# UBX_NORA_B1_SCHEM_0005_Interface_Isolati.net
KiCad netlist of a schematic drawn in Altium Designer
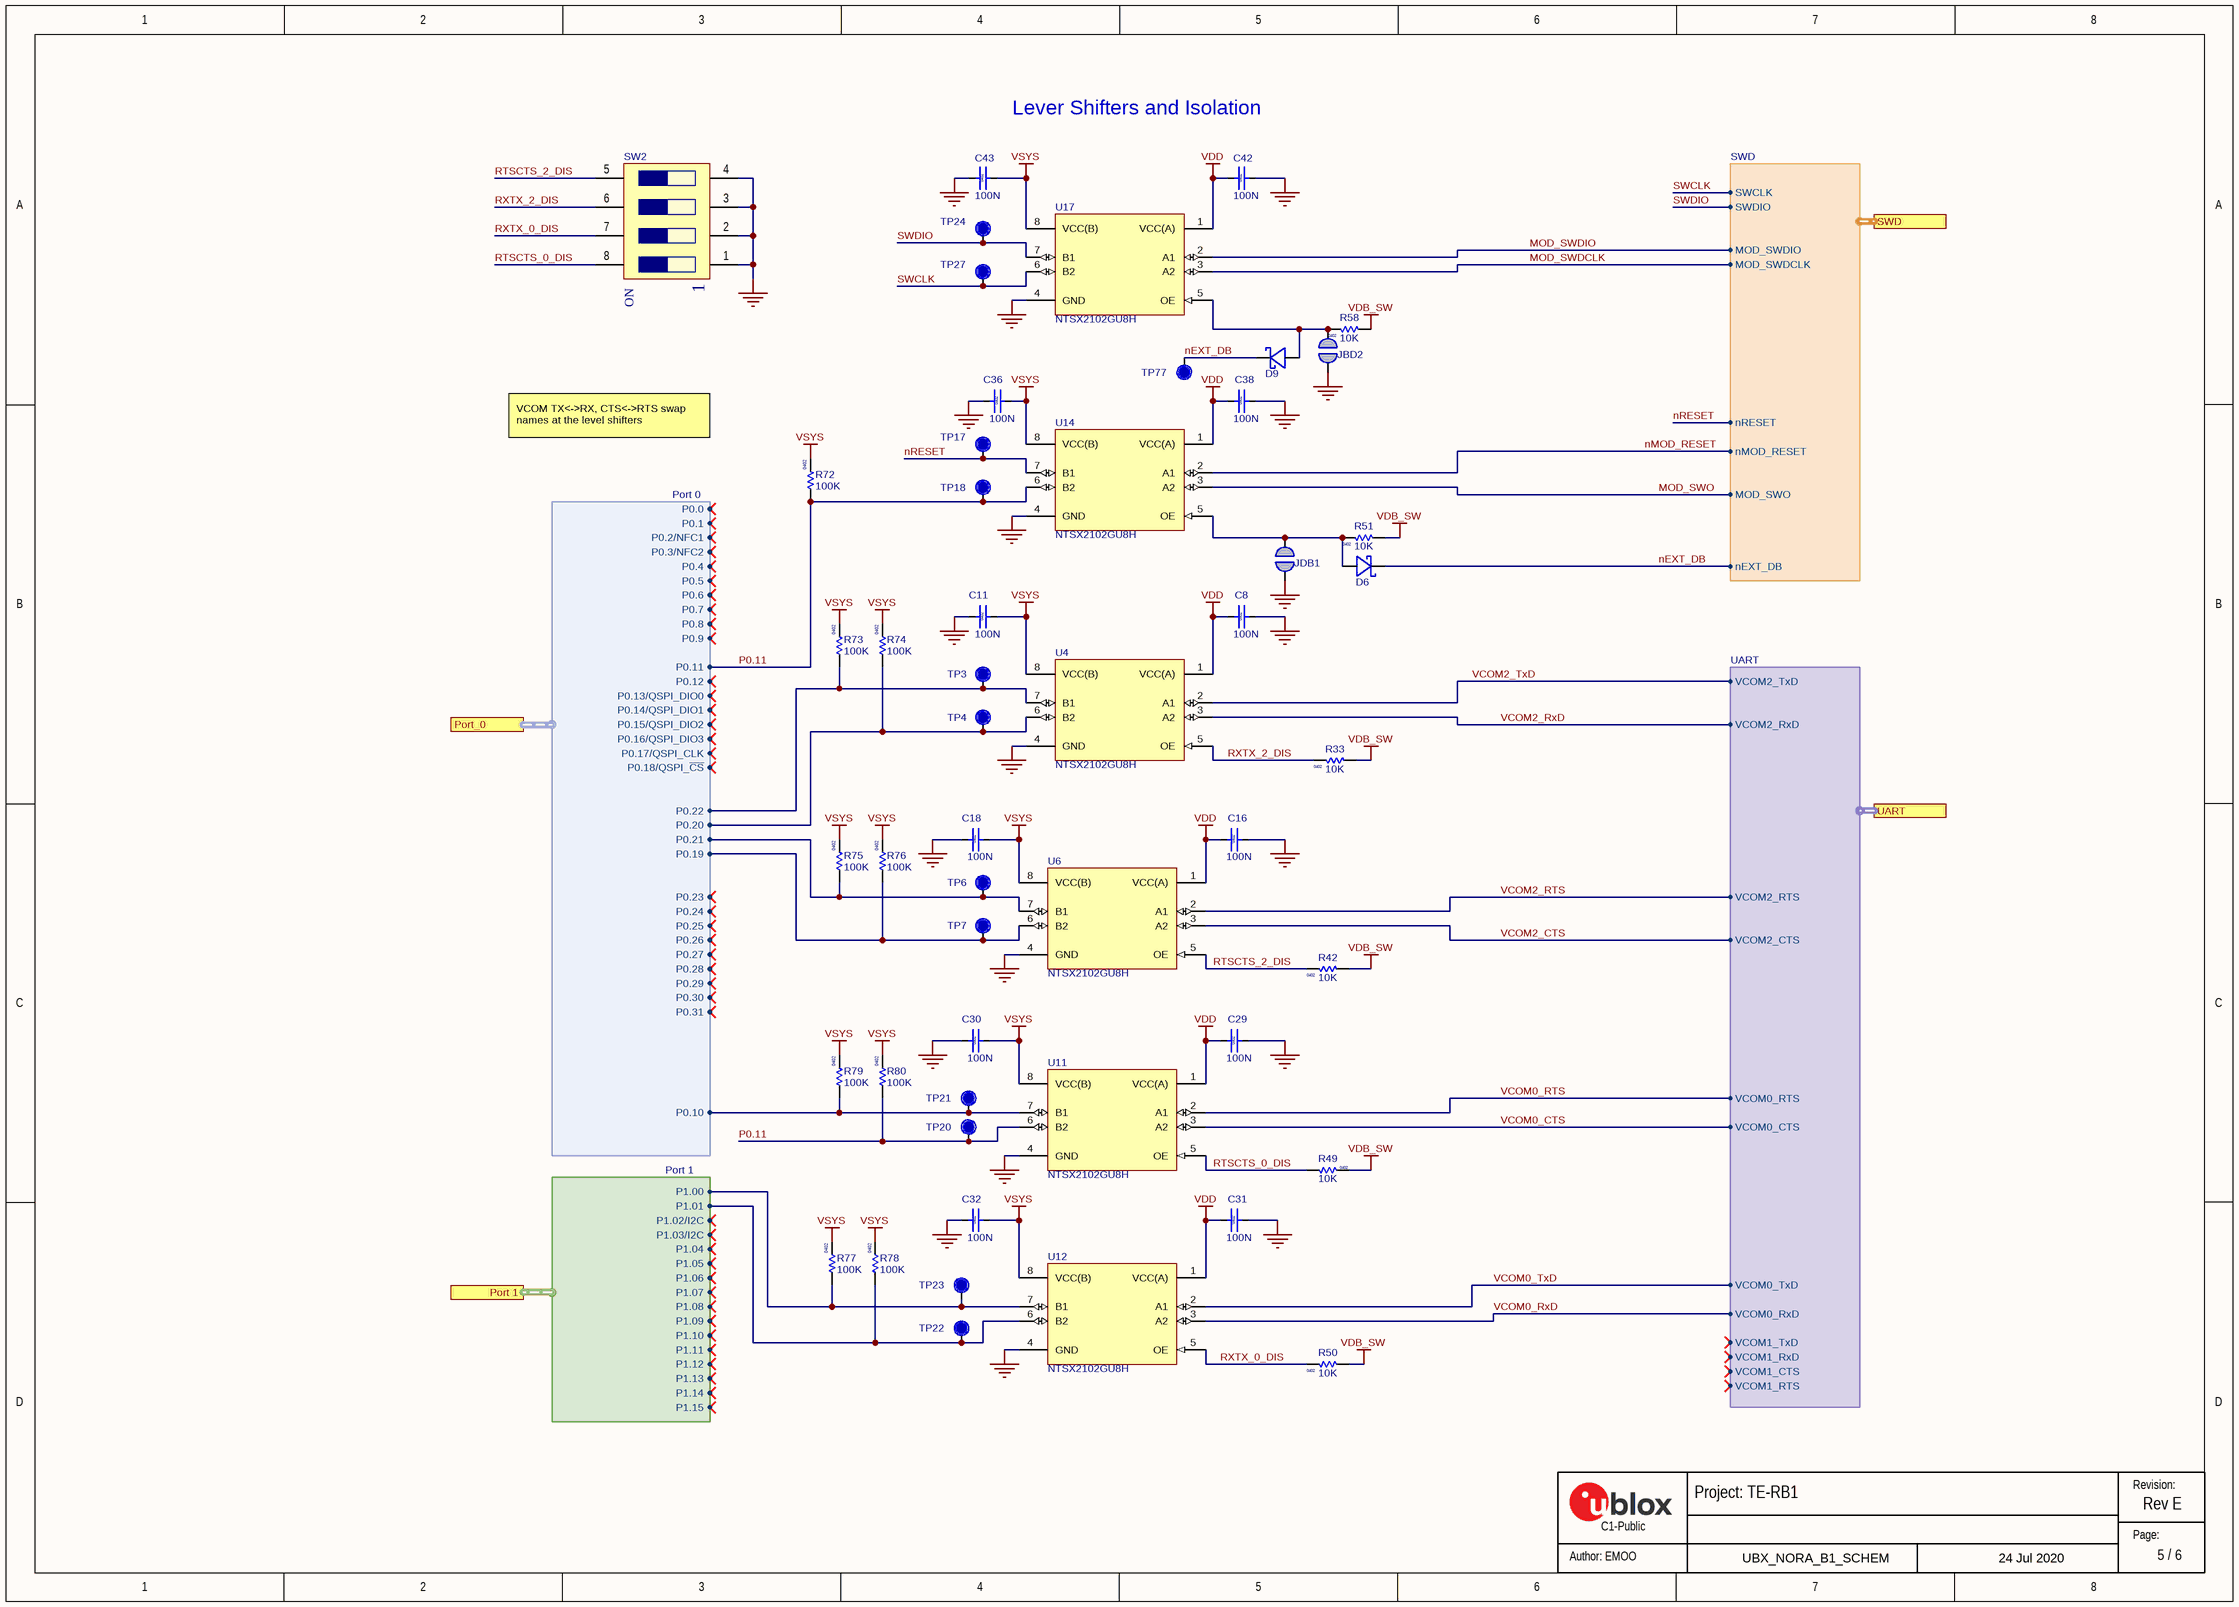
[diagram p0: UBX_NORA_B1_SCHEM_0005_Interface_Isolation.SchDoc]

(export (version "E")
  (design (tool "Eeschema 10.0.6"))
  (components
    (comp (ref "C8")
      (value "100N")
      (footprint "Cap 0402 HD")
      (description "CAP CER X5R 0402 100N 10% 10V")
      (fields
        (field (name "SIZE") "0402")
        (field (name "PART NUMBER") "UBXH01-2021002")
        (field (name "TOLERANCE") "10%")
        (field (name "EDITOR") "roland.rust")
        (field (name "RELEASED BY") "roland.rust")
      )
      (libsource (lib "UBX_Parts_DB_Lib") (part "Cap Chip"))
    )
    (comp (ref "C11")
      (value "100N")
      (footprint "Cap 0402 HD")
      (description "CAP CER X5R 0402 100N 10% 10V")
      (fields
        (field (name "SIZE") "0402")
        (field (name "PART NUMBER") "UBXH01-2021002")
        (field (name "TOLERANCE") "10%")
        (field (name "EDITOR") "roland.rust")
        (field (name "RELEASED BY") "roland.rust")
      )
      (libsource (lib "UBX_Parts_DB_Lib") (part "Cap Chip"))
    )
    (comp (ref "C16")
      (value "100N")
      (footprint "Cap 0402 HD")
      (description "CAP CER X5R 0402 100N 10% 10V")
      (fields
        (field (name "SIZE") "0402")
        (field (name "PART NUMBER") "UBXH01-2021002")
        (field (name "TOLERANCE") "10%")
        (field (name "EDITOR") "roland.rust")
        (field (name "RELEASED BY") "roland.rust")
      )
      (libsource (lib "UBX_Parts_DB_Lib") (part "Cap Chip"))
    )
    (comp (ref "C18")
      (value "100N")
      (footprint "Cap 0402 HD")
      (description "CAP CER X5R 0402 100N 10% 10V")
      (fields
        (field (name "SIZE") "0402")
        (field (name "PART NUMBER") "UBXH01-2021002")
        (field (name "TOLERANCE") "10%")
        (field (name "EDITOR") "roland.rust")
        (field (name "RELEASED BY") "roland.rust")
      )
      (libsource (lib "UBX_Parts_DB_Lib") (part "Cap Chip"))
    )
    (comp (ref "C29")
      (value "100N")
      (footprint "Cap 0402 HD")
      (description "CAP CER X5R 0402 100N 10% 10V")
      (fields
        (field (name "SIZE") "0402")
        (field (name "PART NUMBER") "UBXH01-2021002")
        (field (name "TOLERANCE") "10%")
        (field (name "EDITOR") "roland.rust")
        (field (name "RELEASED BY") "roland.rust")
      )
      (libsource (lib "UBX_Parts_DB_Lib") (part "Cap Chip"))
    )
    (comp (ref "C30")
      (value "100N")
      (footprint "Cap 0402 HD")
      (description "CAP CER X5R 0402 100N 10% 10V")
      (fields
        (field (name "SIZE") "0402")
        (field (name "PART NUMBER") "UBXH01-2021002")
        (field (name "TOLERANCE") "10%")
        (field (name "EDITOR") "roland.rust")
        (field (name "RELEASED BY") "roland.rust")
      )
      (libsource (lib "UBX_Parts_DB_Lib") (part "Cap Chip"))
    )
    (comp (ref "C31")
      (value "100N")
      (footprint "Cap 0402 HD")
      (description "CAP CER X5R 0402 100N 10% 10V")
      (fields
        (field (name "SIZE") "0402")
        (field (name "PART NUMBER") "UBXH01-2021002")
        (field (name "TOLERANCE") "10%")
        (field (name "EDITOR") "roland.rust")
        (field (name "RELEASED BY") "roland.rust")
      )
      (libsource (lib "UBX_Parts_DB_Lib") (part "Cap Chip"))
    )
    (comp (ref "C32")
      (value "100N")
      (footprint "Cap 0402 HD")
      (description "CAP CER X5R 0402 100N 10% 10V")
      (fields
        (field (name "SIZE") "0402")
        (field (name "PART NUMBER") "UBXH01-2021002")
        (field (name "TOLERANCE") "10%")
        (field (name "EDITOR") "roland.rust")
        (field (name "RELEASED BY") "roland.rust")
      )
      (libsource (lib "UBX_Parts_DB_Lib") (part "Cap Chip"))
    )
    (comp (ref "C36")
      (value "100N")
      (footprint "Cap 0402 HD")
      (description "CAP CER X5R 0402 100N 10% 10V")
      (fields
        (field (name "SIZE") "0402")
        (field (name "PART NUMBER") "UBXH01-2021002")
        (field (name "TOLERANCE") "10%")
        (field (name "EDITOR") "roland.rust")
        (field (name "RELEASED BY") "roland.rust")
      )
      (libsource (lib "UBX_Parts_DB_Lib") (part "Cap Chip"))
    )
    (comp (ref "C38")
      (value "100N")
      (footprint "Cap 0402 HD")
      (description "CAP CER X5R 0402 100N 10% 10V")
      (fields
        (field (name "SIZE") "0402")
        (field (name "PART NUMBER") "UBXH01-2021002")
        (field (name "TOLERANCE") "10%")
        (field (name "EDITOR") "roland.rust")
        (field (name "RELEASED BY") "roland.rust")
      )
      (libsource (lib "UBX_Parts_DB_Lib") (part "Cap Chip"))
    )
    (comp (ref "C42")
      (value "100N")
      (footprint "Cap 0402 HD")
      (description "CAP CER X5R 0402 100N 10% 10V")
      (fields
        (field (name "SIZE") "0402")
        (field (name "PART NUMBER") "UBXH01-2021002")
        (field (name "TOLERANCE") "10%")
        (field (name "EDITOR") "roland.rust")
        (field (name "RELEASED BY") "roland.rust")
      )
      (libsource (lib "UBX_Parts_DB_Lib") (part "Cap Chip"))
    )
    (comp (ref "C43")
      (value "100N")
      (footprint "Cap 0402 HD")
      (description "CAP CER X5R 0402 100N 10% 10V")
      (fields
        (field (name "SIZE") "0402")
        (field (name "PART NUMBER") "UBXH01-2021002")
        (field (name "TOLERANCE") "10%")
        (field (name "EDITOR") "roland.rust")
        (field (name "RELEASED BY") "roland.rust")
      )
      (libsource (lib "UBX_Parts_DB_Lib") (part "Cap Chip"))
    )
    (comp (ref "D6")
      (value "UBXH07-0000039")
      (footprint "SOD-523")
      (description "SCHOTTKY BARRIER DIODE 30V 200mA")
      (fields
        (field (name "MANUFACTURER") "ON Semiconductor")
        (field (name "EDITOR") "matej.budin")
        (field (name "RELEASED BY") "pierpaolo.arban")
      )
      (libsource (lib "UBX_Parts_DB_Lib") (part "Diode_Schottky"))
    )
    (comp (ref "D9")
      (value "UBXH07-0000039")
      (footprint "SOD-523")
      (description "SCHOTTKY BARRIER DIODE 30V 200mA")
      (fields
        (field (name "MANUFACTURER") "ON Semiconductor")
        (field (name "EDITOR") "matej.budin")
        (field (name "RELEASED BY") "pierpaolo.arban")
      )
      (libsource (lib "UBX_Parts_DB_Lib") (part "Diode_Schottky"))
    )
    (comp (ref "JBD2")
      (value "UBXH00-0000082")
      (footprint "Solderbridge-Open")
      (description "SOLDERBRIDGE-OPEN")
      (fields (field (name "EDITOR") "aneeb.sohail"))
      (libsource (lib "UBX_Parts_DB_Lib") (part "Solderbridge-Open"))
    )
    (comp (ref "JDB1")
      (value "UBXH00-0000082")
      (footprint "Solderbridge-Open")
      (description "SOLDERBRIDGE-OPEN")
      (fields (field (name "EDITOR") "aneeb.sohail"))
      (libsource (lib "UBX_Parts_DB_Lib") (part "Solderbridge-Open"))
    )
    (comp (ref "R33")
      (value "10K")
      (footprint "RES 0402 HD")
      (description "RES THICK FILM CHIP 0402 10K 1% 63mW")
      (fields
        (field (name "SIZE") "0402")
        (field (name "PART NUMBER") "UBXH18-0000065")
        (field (name "TOLERANCE") "1%")
        (field (name "EDITOR") "erian.bezhani")
        (field (name "RELEASED BY") "massimo.vlacci")
      )
      (libsource (lib "UBX_Parts_DB_Lib") (part "Res sm"))
    )
    (comp (ref "R42")
      (value "10K")
      (footprint "RES 0402 HD")
      (description "RES THICK FILM CHIP 0402 10K 1% 63mW")
      (fields
        (field (name "SIZE") "0402")
        (field (name "PART NUMBER") "UBXH18-0000065")
        (field (name "TOLERANCE") "1%")
        (field (name "EDITOR") "erian.bezhani")
        (field (name "RELEASED BY") "massimo.vlacci")
      )
      (libsource (lib "UBX_Parts_DB_Lib") (part "Res sm"))
    )
    (comp (ref "R49")
      (value "10K")
      (footprint "RES 0402 HD")
      (description "RES THICK FILM CHIP 0402 10K 1% 63mW")
      (fields
        (field (name "SIZE") "0402")
        (field (name "PART NUMBER") "UBXH18-0000065")
        (field (name "TOLERANCE") "1%")
        (field (name "EDITOR") "erian.bezhani")
        (field (name "RELEASED BY") "massimo.vlacci")
      )
      (libsource (lib "UBX_Parts_DB_Lib") (part "Res sm"))
    )
    (comp (ref "R50")
      (value "10K")
      (footprint "RES 0402 HD")
      (description "RES THICK FILM CHIP 0402 10K 1% 63mW")
      (fields
        (field (name "SIZE") "0402")
        (field (name "PART NUMBER") "UBXH18-0000065")
        (field (name "TOLERANCE") "1%")
        (field (name "EDITOR") "erian.bezhani")
        (field (name "RELEASED BY") "massimo.vlacci")
      )
      (libsource (lib "UBX_Parts_DB_Lib") (part "Res sm"))
    )
    (comp (ref "R51")
      (value "10K")
      (footprint "RES 0402 HD")
      (description "RES THICK FILM CHIP 0402 10K 1% 63mW")
      (fields
        (field (name "SIZE") "0402")
        (field (name "PART NUMBER") "UBXH18-0000065")
        (field (name "TOLERANCE") "1%")
        (field (name "EDITOR") "erian.bezhani")
        (field (name "RELEASED BY") "massimo.vlacci")
      )
      (libsource (lib "UBX_Parts_DB_Lib") (part "Res sm"))
    )
    (comp (ref "R58")
      (value "10K")
      (footprint "RES 0402 HD")
      (description "RES THICK FILM CHIP 0402 10K 1% 63mW")
      (fields
        (field (name "SIZE") "0402")
        (field (name "PART NUMBER") "UBXH18-0000065")
        (field (name "TOLERANCE") "1%")
        (field (name "EDITOR") "erian.bezhani")
        (field (name "RELEASED BY") "massimo.vlacci")
      )
      (libsource (lib "UBX_Parts_DB_Lib") (part "Res sm"))
    )
    (comp (ref "R72")
      (value "100K")
      (footprint "RES 0402 HD")
      (description "RES THICK FILM CHIP 0402 100K 1% 63mW")
      (fields
        (field (name "SIZE") "0402")
        (field (name "PART NUMBER") "UBXH18-0000005")
        (field (name "TOLERANCE") "1%")
        (field (name "EDITOR") "dario.antonaz")
        (field (name "RELEASED BY") "sandro.sestan")
      )
      (libsource (lib "UBX_Parts_DB_Lib") (part "Res sm"))
    )
    (comp (ref "R73")
      (value "100K")
      (footprint "RES 0402 HD")
      (description "RES THICK FILM CHIP 0402 100K 1% 63mW")
      (fields
        (field (name "SIZE") "0402")
        (field (name "PART NUMBER") "UBXH18-0000005")
        (field (name "TOLERANCE") "1%")
        (field (name "EDITOR") "dario.antonaz")
        (field (name "RELEASED BY") "sandro.sestan")
      )
      (libsource (lib "UBX_Parts_DB_Lib") (part "Res sm"))
    )
    (comp (ref "R74")
      (value "100K")
      (footprint "RES 0402 HD")
      (description "RES THICK FILM CHIP 0402 100K 1% 63mW")
      (fields
        (field (name "SIZE") "0402")
        (field (name "PART NUMBER") "UBXH18-0000005")
        (field (name "TOLERANCE") "1%")
        (field (name "EDITOR") "dario.antonaz")
        (field (name "RELEASED BY") "sandro.sestan")
      )
      (libsource (lib "UBX_Parts_DB_Lib") (part "Res sm"))
    )
    (comp (ref "R75")
      (value "100K")
      (footprint "RES 0402 HD")
      (description "RES THICK FILM CHIP 0402 100K 1% 63mW")
      (fields
        (field (name "SIZE") "0402")
        (field (name "PART NUMBER") "UBXH18-0000005")
        (field (name "TOLERANCE") "1%")
        (field (name "EDITOR") "dario.antonaz")
        (field (name "RELEASED BY") "sandro.sestan")
      )
      (libsource (lib "UBX_Parts_DB_Lib") (part "Res sm"))
    )
    (comp (ref "R76")
      (value "100K")
      (footprint "RES 0402 HD")
      (description "RES THICK FILM CHIP 0402 100K 1% 63mW")
      (fields
        (field (name "SIZE") "0402")
        (field (name "PART NUMBER") "UBXH18-0000005")
        (field (name "TOLERANCE") "1%")
        (field (name "EDITOR") "dario.antonaz")
        (field (name "RELEASED BY") "sandro.sestan")
      )
      (libsource (lib "UBX_Parts_DB_Lib") (part "Res sm"))
    )
    (comp (ref "R77")
      (value "100K")
      (footprint "RES 0402 HD")
      (description "RES THICK FILM CHIP 0402 100K 1% 63mW")
      (fields
        (field (name "SIZE") "0402")
        (field (name "PART NUMBER") "UBXH18-0000005")
        (field (name "TOLERANCE") "1%")
        (field (name "EDITOR") "dario.antonaz")
        (field (name "RELEASED BY") "sandro.sestan")
      )
      (libsource (lib "UBX_Parts_DB_Lib") (part "Res sm"))
    )
    (comp (ref "R78")
      (value "100K")
      (footprint "RES 0402 HD")
      (description "RES THICK FILM CHIP 0402 100K 1% 63mW")
      (fields
        (field (name "SIZE") "0402")
        (field (name "PART NUMBER") "UBXH18-0000005")
        (field (name "TOLERANCE") "1%")
        (field (name "EDITOR") "dario.antonaz")
        (field (name "RELEASED BY") "sandro.sestan")
      )
      (libsource (lib "UBX_Parts_DB_Lib") (part "Res sm"))
    )
    (comp (ref "R79")
      (value "100K")
      (footprint "RES 0402 HD")
      (description "RES THICK FILM CHIP 0402 100K 1% 63mW")
      (fields
        (field (name "SIZE") "0402")
        (field (name "PART NUMBER") "UBXH18-0000005")
        (field (name "TOLERANCE") "1%")
        (field (name "EDITOR") "dario.antonaz")
        (field (name "RELEASED BY") "sandro.sestan")
      )
      (libsource (lib "UBX_Parts_DB_Lib") (part "Res sm"))
    )
    (comp (ref "R80")
      (value "100K")
      (footprint "RES 0402 HD")
      (description "RES THICK FILM CHIP 0402 100K 1% 63mW")
      (fields
        (field (name "SIZE") "0402")
        (field (name "PART NUMBER") "UBXH18-0000005")
        (field (name "TOLERANCE") "1%")
        (field (name "EDITOR") "dario.antonaz")
        (field (name "RELEASED BY") "sandro.sestan")
      )
      (libsource (lib "UBX_Parts_DB_Lib") (part "Res sm"))
    )
    (comp (ref "SW2")
      (value "UBXH19-0000055")
      (footprint "SOP1.27P6.2x6.2-8Pin")
      (description "DIP SWITCH QUAD SPST SLIDE SMT 24V 25mA")
      (fields (field (name "EDITOR") "eric.moog"))
      (libsource (lib "UBX_Parts_DB_Lib") (part "SW_DIP_4POS_SPST"))
    )
    (comp (ref "TP3")
      (value "TP")
      (footprint "TP10R")
      (description "TESTPOINT 1MM CIRCULAR")
      (fields (field (name "PART NUMBER") "UBXH00-0000096") (field (name "EDITOR") "eric.moog"))
      (libsource (lib "UBX_Parts_DB_Lib") (part "TP_R"))
    )
    (comp (ref "TP4")
      (value "TP")
      (footprint "TP10R")
      (description "TESTPOINT 1MM CIRCULAR")
      (fields (field (name "PART NUMBER") "UBXH00-0000096") (field (name "EDITOR") "eric.moog"))
      (libsource (lib "UBX_Parts_DB_Lib") (part "TP_R"))
    )
    (comp (ref "TP6")
      (value "TP")
      (footprint "TP10R")
      (description "TESTPOINT 1MM CIRCULAR")
      (fields (field (name "PART NUMBER") "UBXH00-0000096") (field (name "EDITOR") "eric.moog"))
      (libsource (lib "UBX_Parts_DB_Lib") (part "TP_R"))
    )
    (comp (ref "TP7")
      (value "TP")
      (footprint "TP10R")
      (description "TESTPOINT 1MM CIRCULAR")
      (fields (field (name "PART NUMBER") "UBXH00-0000096") (field (name "EDITOR") "eric.moog"))
      (libsource (lib "UBX_Parts_DB_Lib") (part "TP_R"))
    )
    (comp (ref "TP17")
      (value "TP")
      (footprint "TP10R")
      (description "TESTPOINT 1MM CIRCULAR")
      (fields (field (name "PART NUMBER") "UBXH00-0000096") (field (name "EDITOR") "eric.moog"))
      (libsource (lib "UBX_Parts_DB_Lib") (part "TP_R"))
    )
    (comp (ref "TP18")
      (value "TP")
      (footprint "TP10R")
      (description "TESTPOINT 1MM CIRCULAR")
      (fields (field (name "PART NUMBER") "UBXH00-0000096") (field (name "EDITOR") "eric.moog"))
      (libsource (lib "UBX_Parts_DB_Lib") (part "TP_R"))
    )
    (comp (ref "TP20")
      (value "TP")
      (footprint "TP10R")
      (description "TESTPOINT 1MM CIRCULAR")
      (fields (field (name "PART NUMBER") "UBXH00-0000096") (field (name "EDITOR") "eric.moog"))
      (libsource (lib "UBX_Parts_DB_Lib") (part "TP_R"))
    )
    (comp (ref "TP21")
      (value "TP")
      (footprint "TP10R")
      (description "TESTPOINT 1MM CIRCULAR")
      (fields (field (name "PART NUMBER") "UBXH00-0000096") (field (name "EDITOR") "eric.moog"))
      (libsource (lib "UBX_Parts_DB_Lib") (part "TP_R"))
    )
    (comp (ref "TP22")
      (value "TP")
      (footprint "TP10R")
      (description "TESTPOINT 1MM CIRCULAR")
      (fields (field (name "PART NUMBER") "UBXH00-0000096") (field (name "EDITOR") "eric.moog"))
      (libsource (lib "UBX_Parts_DB_Lib") (part "TP_R"))
    )
    (comp (ref "TP23")
      (value "TP")
      (footprint "TP10R")
      (description "TESTPOINT 1MM CIRCULAR")
      (fields (field (name "PART NUMBER") "UBXH00-0000096") (field (name "EDITOR") "eric.moog"))
      (libsource (lib "UBX_Parts_DB_Lib") (part "TP_R"))
    )
    (comp (ref "TP24")
      (value "TP")
      (footprint "TP10R")
      (description "TESTPOINT 1MM CIRCULAR")
      (fields (field (name "PART NUMBER") "UBXH00-0000096") (field (name "EDITOR") "eric.moog"))
      (libsource (lib "UBX_Parts_DB_Lib") (part "TP_R"))
    )
    (comp (ref "TP27")
      (value "TP")
      (footprint "TP10R")
      (description "TESTPOINT 1MM CIRCULAR")
      (fields (field (name "PART NUMBER") "UBXH00-0000096") (field (name "EDITOR") "eric.moog"))
      (libsource (lib "UBX_Parts_DB_Lib") (part "TP_R"))
    )
    (comp (ref "TP77")
      (value "TP")
      (footprint "TP10R")
      (description "TESTPOINT 1MM CIRCULAR")
      (fields (field (name "PART NUMBER") "UBXH00-0000096") (field (name "EDITOR") "eric.moog"))
      (libsource (lib "UBX_Parts_DB_Lib") (part "TP_R"))
    )
    (comp (ref "U4")
      (value "UBXH10-0000106")
      (footprint "QFN0.4P3x1-8Pin")
      (description "2-BIT BIDIRECTIONAL TRANSLATING TRANSCEIVER AUTO DIRECTION SENSING OPEN DRAIN XQFN8 5.5V")
      (fields
        (field (name "VOLTAGE") "5.5V")
        (field (name "MANUFACTURER PART NUMBER 1") "NTSX2102GU8H")
        (field (name "MANUFACTURER") "NXP")
        (field (name "EDITOR") "eric.moog")
      )
      (libsource (lib "UBX_Parts_DB_Lib") (part "NTSX2102GU8"))
    )
    (comp (ref "U6")
      (value "UBXH10-0000106")
      (footprint "QFN0.4P3x1-8Pin")
      (description "2-BIT BIDIRECTIONAL TRANSLATING TRANSCEIVER AUTO DIRECTION SENSING OPEN DRAIN XQFN8 5.5V")
      (fields
        (field (name "VOLTAGE") "5.5V")
        (field (name "MANUFACTURER PART NUMBER 1") "NTSX2102GU8H")
        (field (name "MANUFACTURER") "NXP")
        (field (name "EDITOR") "eric.moog")
      )
      (libsource (lib "UBX_Parts_DB_Lib") (part "NTSX2102GU8"))
    )
    (comp (ref "U11")
      (value "UBXH10-0000106")
      (footprint "QFN0.4P3x1-8Pin")
      (description "2-BIT BIDIRECTIONAL TRANSLATING TRANSCEIVER AUTO DIRECTION SENSING OPEN DRAIN XQFN8 5.5V")
      (fields
        (field (name "VOLTAGE") "5.5V")
        (field (name "MANUFACTURER PART NUMBER 1") "NTSX2102GU8H")
        (field (name "MANUFACTURER") "NXP")
        (field (name "EDITOR") "eric.moog")
      )
      (libsource (lib "UBX_Parts_DB_Lib") (part "NTSX2102GU8"))
    )
    (comp (ref "U12")
      (value "UBXH10-0000106")
      (footprint "QFN0.4P3x1-8Pin")
      (description "2-BIT BIDIRECTIONAL TRANSLATING TRANSCEIVER AUTO DIRECTION SENSING OPEN DRAIN XQFN8 5.5V")
      (fields
        (field (name "VOLTAGE") "5.5V")
        (field (name "MANUFACTURER PART NUMBER 1") "NTSX2102GU8H")
        (field (name "MANUFACTURER") "NXP")
        (field (name "EDITOR") "eric.moog")
      )
      (libsource (lib "UBX_Parts_DB_Lib") (part "NTSX2102GU8"))
    )
    (comp (ref "U14")
      (value "UBXH10-0000106")
      (footprint "QFN0.4P3x1-8Pin")
      (description "2-BIT BIDIRECTIONAL TRANSLATING TRANSCEIVER AUTO DIRECTION SENSING OPEN DRAIN XQFN8 5.5V")
      (fields
        (field (name "VOLTAGE") "5.5V")
        (field (name "MANUFACTURER PART NUMBER 1") "NTSX2102GU8H")
        (field (name "MANUFACTURER") "NXP")
        (field (name "EDITOR") "eric.moog")
      )
      (libsource (lib "UBX_Parts_DB_Lib") (part "NTSX2102GU8"))
    )
    (comp (ref "U17")
      (value "UBXH10-0000106")
      (footprint "QFN0.4P3x1-8Pin")
      (description "2-BIT BIDIRECTIONAL TRANSLATING TRANSCEIVER AUTO DIRECTION SENSING OPEN DRAIN XQFN8 5.5V")
      (fields
        (field (name "VOLTAGE") "5.5V")
        (field (name "MANUFACTURER PART NUMBER 1") "NTSX2102GU8H")
        (field (name "MANUFACTURER") "NXP")
        (field (name "EDITOR") "eric.moog")
      )
      (libsource (lib "UBX_Parts_DB_Lib") (part "NTSX2102GU8"))
    )
  )
  (nets
    (net (code "6") (name "/MOD_SWDCLK") (class "Default")
      (node (ref "U17") (pin "3") (pinfunction "A2_3") (pintype "bidirectional"))
    )
    (net (code "7") (name "/MOD_SWDIO") (class "Default")
      (node (ref "U17") (pin "2") (pinfunction "A1_2") (pintype "bidirectional"))
    )
    (net (code "8") (name "/MOD_SWO") (class "Default")
      (node (ref "U14") (pin "3") (pinfunction "A2_3") (pintype "bidirectional"))
    )
    (net (code "9") (name "/P0.11") (class "Default")
      (node (ref "R72") (pin "1") (pinfunction "1_1") (pintype "passive"))
      (node (ref "R80") (pin "1") (pinfunction "1_1") (pintype "passive"))
      (node (ref "TP18") (pin "1") (pintype "passive"))
      (node (ref "TP20") (pin "1") (pintype "passive"))
      (node (ref "U11") (pin "6") (pinfunction "B2_6") (pintype "bidirectional"))
      (node (ref "U14") (pin "6") (pinfunction "B2_6") (pintype "bidirectional"))
    )
    (net (code "10") (name "/RTSCTS_0_DIS") (class "Default")
      (node (ref "R49") (pin "1") (pinfunction "1_1") (pintype "passive"))
      (node (ref "SW2") (pin "8") (pintype "passive"))
      (node (ref "U11") (pin "5") (pinfunction "OE_5") (pintype "input"))
    )
    (net (code "11") (name "/RTSCTS_2_DIS") (class "Default")
      (node (ref "R42") (pin "2") (pinfunction "2_2") (pintype "passive"))
      (node (ref "SW2") (pin "5") (pintype "passive"))
      (node (ref "U6") (pin "5") (pinfunction "OE_5") (pintype "input"))
    )
    (net (code "12") (name "/RXTX_0_DIS") (class "Default")
      (node (ref "R50") (pin "2") (pinfunction "2_2") (pintype "passive"))
      (node (ref "SW2") (pin "7") (pintype "passive"))
      (node (ref "U12") (pin "5") (pinfunction "OE_5") (pintype "input"))
    )
    (net (code "13") (name "/RXTX_2_DIS") (class "Default")
      (node (ref "R33") (pin "2") (pinfunction "2_2") (pintype "passive"))
      (node (ref "SW2") (pin "6") (pintype "passive"))
      (node (ref "U4") (pin "5") (pinfunction "OE_5") (pintype "input"))
    )
    (net (code "14") (name "/SWCLK") (class "Default")
      (node (ref "TP27") (pin "1") (pintype "passive"))
      (node (ref "U17") (pin "6") (pinfunction "B2_6") (pintype "bidirectional"))
    )
    (net (code "15") (name "/SWDIO") (class "Default")
      (node (ref "TP24") (pin "1") (pintype "passive"))
      (node (ref "U17") (pin "7") (pinfunction "B1_7") (pintype "bidirectional"))
    )
    (net (code "16") (name "/VCOM0_CTS") (class "Default")
      (node (ref "U11") (pin "3") (pinfunction "A2_3") (pintype "bidirectional"))
    )
    (net (code "17") (name "/VCOM0_RTS") (class "Default")
      (node (ref "U11") (pin "2") (pinfunction "A1_2") (pintype "bidirectional"))
    )
    (net (code "18") (name "/VCOM0_RxD") (class "Default")
      (node (ref "U12") (pin "3") (pinfunction "A2_3") (pintype "bidirectional"))
    )
    (net (code "19") (name "/VCOM0_TxD") (class "Default")
      (node (ref "U12") (pin "2") (pinfunction "A1_2") (pintype "bidirectional"))
    )
    (net (code "20") (name "/VCOM2_CTS") (class "Default")
      (node (ref "U6") (pin "3") (pinfunction "A2_3") (pintype "bidirectional"))
    )
    (net (code "21") (name "/VCOM2_RTS") (class "Default")
      (node (ref "U6") (pin "2") (pinfunction "A1_2") (pintype "bidirectional"))
    )
    (net (code "22") (name "/VCOM2_RxD") (class "Default")
      (node (ref "U4") (pin "3") (pinfunction "A2_3") (pintype "bidirectional"))
    )
    (net (code "23") (name "/VCOM2_TxD") (class "Default")
      (node (ref "U4") (pin "2") (pinfunction "A1_2") (pintype "bidirectional"))
    )
    (net (code "24") (name "/nEXT_DB") (class "Default")
      (node (ref "D6") (pin "C") (pinfunction "Cathode_C") (pintype "passive"))
      (node (ref "D9") (pin "C") (pinfunction "Cathode_C") (pintype "passive"))
      (node (ref "TP77") (pin "1") (pintype "passive"))
    )
    (net (code "25") (name "/nMOD_RESET") (class "Default")
      (node (ref "U14") (pin "2") (pinfunction "A1_2") (pintype "bidirectional"))
    )
    (net (code "26") (name "/nRESET") (class "Default")
      (node (ref "TP17") (pin "1") (pintype "passive"))
      (node (ref "U14") (pin "7") (pinfunction "B1_7") (pintype "bidirectional"))
    )
    (net (code "31") (name "GND") (class "Default")
      (node (ref "C11") (pin "1") (pinfunction "1_1") (pintype "passive"))
      (node (ref "C16") (pin "2") (pinfunction "2_2") (pintype "passive"))
      (node (ref "C18") (pin "1") (pinfunction "1_1") (pintype "passive"))
      (node (ref "C29") (pin "2") (pinfunction "2_2") (pintype "passive"))
      (node (ref "C30") (pin "1") (pinfunction "1_1") (pintype "passive"))
      (node (ref "C31") (pin "2") (pinfunction "2_2") (pintype "passive"))
      (node (ref "C32") (pin "1") (pinfunction "1_1") (pintype "passive"))
      (node (ref "C36") (pin "1") (pinfunction "1_1") (pintype "passive"))
      (node (ref "C38") (pin "2") (pinfunction "2_2") (pintype "passive"))
      (node (ref "C42") (pin "2") (pinfunction "2_2") (pintype "passive"))
      (node (ref "C43") (pin "1") (pinfunction "1_1") (pintype "passive"))
      (node (ref "C8") (pin "2") (pinfunction "2_2") (pintype "passive"))
      (node (ref "JBD2") (pin "1") (pinfunction "1_1") (pintype "passive"))
      (node (ref "JDB1") (pin "1") (pinfunction "1_1") (pintype "passive"))
      (node (ref "SW2") (pin "1") (pintype "passive"))
      (node (ref "SW2") (pin "2") (pintype "passive"))
      (node (ref "SW2") (pin "3") (pintype "passive"))
      (node (ref "SW2") (pin "4") (pintype "passive"))
      (node (ref "U11") (pin "4") (pinfunction "GND_4") (pintype "power_in"))
      (node (ref "U12") (pin "4") (pinfunction "GND_4") (pintype "power_in"))
      (node (ref "U14") (pin "4") (pinfunction "GND_4") (pintype "power_in"))
      (node (ref "U17") (pin "4") (pinfunction "GND_4") (pintype "power_in"))
      (node (ref "U4") (pin "4") (pinfunction "GND_4") (pintype "power_in"))
      (node (ref "U6") (pin "4") (pinfunction "GND_4") (pintype "power_in"))
    )
    (net (code "32") (name "Net-(D6-Anode)") (class "Default")
      (node (ref "D6") (pin "A") (pinfunction "Anode_A") (pintype "passive"))
      (node (ref "JDB1") (pin "2") (pinfunction "2_2") (pintype "passive"))
      (node (ref "R51") (pin "2") (pinfunction "2_2") (pintype "passive"))
      (node (ref "U14") (pin "5") (pinfunction "OE_5") (pintype "input"))
    )
    (net (code "33") (name "Net-(D9-Anode)") (class "Default")
      (node (ref "D9") (pin "A") (pinfunction "Anode_A") (pintype "passive"))
      (node (ref "JBD2") (pin "2") (pinfunction "2_2") (pintype "passive"))
      (node (ref "R58") (pin "2") (pinfunction "2_2") (pintype "passive"))
      (node (ref "U17") (pin "5") (pinfunction "OE_5") (pintype "input"))
    )
    (net (code "34") (name "Net-(U4-B1)") (class "Default")
      (node (ref "R73") (pin "1") (pinfunction "1_1") (pintype "passive"))
      (node (ref "TP3") (pin "1") (pintype "passive"))
      (node (ref "U4") (pin "7") (pinfunction "B1_7") (pintype "bidirectional"))
    )
    (net (code "35") (name "Net-(U4-B2)") (class "Default")
      (node (ref "R74") (pin "1") (pinfunction "1_1") (pintype "passive"))
      (node (ref "TP4") (pin "1") (pintype "passive"))
      (node (ref "U4") (pin "6") (pinfunction "B2_6") (pintype "bidirectional"))
    )
    (net (code "36") (name "Net-(U6-B1)") (class "Default")
      (node (ref "R75") (pin "1") (pinfunction "1_1") (pintype "passive"))
      (node (ref "TP6") (pin "1") (pintype "passive"))
      (node (ref "U6") (pin "7") (pinfunction "B1_7") (pintype "bidirectional"))
    )
    (net (code "37") (name "Net-(U6-B2)") (class "Default")
      (node (ref "R76") (pin "1") (pinfunction "1_1") (pintype "passive"))
      (node (ref "TP7") (pin "1") (pintype "passive"))
      (node (ref "U6") (pin "6") (pinfunction "B2_6") (pintype "bidirectional"))
    )
    (net (code "38") (name "Net-(U11-B1)") (class "Default")
      (node (ref "R79") (pin "1") (pinfunction "1_1") (pintype "passive"))
      (node (ref "TP21") (pin "1") (pintype "passive"))
      (node (ref "U11") (pin "7") (pinfunction "B1_7") (pintype "bidirectional"))
    )
    (net (code "39") (name "Net-(U12-B1)") (class "Default")
      (node (ref "R77") (pin "1") (pinfunction "1_1") (pintype "passive"))
      (node (ref "TP23") (pin "1") (pintype "passive"))
      (node (ref "U12") (pin "7") (pinfunction "B1_7") (pintype "bidirectional"))
    )
    (net (code "40") (name "Net-(U12-B2)") (class "Default")
      (node (ref "R78") (pin "1") (pinfunction "1_1") (pintype "passive"))
      (node (ref "TP22") (pin "1") (pintype "passive"))
      (node (ref "U12") (pin "6") (pinfunction "B2_6") (pintype "bidirectional"))
    )
    (net (code "41") (name "VDB_SW") (class "Default")
      (node (ref "R33") (pin "1") (pinfunction "1_1") (pintype "passive"))
      (node (ref "R42") (pin "1") (pinfunction "1_1") (pintype "passive"))
      (node (ref "R49") (pin "2") (pinfunction "2_2") (pintype "passive"))
      (node (ref "R50") (pin "1") (pinfunction "1_1") (pintype "passive"))
      (node (ref "R51") (pin "1") (pinfunction "1_1") (pintype "passive"))
      (node (ref "R58") (pin "1") (pinfunction "1_1") (pintype "passive"))
    )
    (net (code "42") (name "VDD") (class "Default")
      (node (ref "C16") (pin "1") (pinfunction "1_1") (pintype "passive"))
      (node (ref "C29") (pin "1") (pinfunction "1_1") (pintype "passive"))
      (node (ref "C31") (pin "1") (pinfunction "1_1") (pintype "passive"))
      (node (ref "C38") (pin "1") (pinfunction "1_1") (pintype "passive"))
      (node (ref "C42") (pin "1") (pinfunction "1_1") (pintype "passive"))
      (node (ref "C8") (pin "1") (pinfunction "1_1") (pintype "passive"))
      (node (ref "U11") (pin "1") (pinfunction "VCC(A)_1") (pintype "power_in"))
      (node (ref "U12") (pin "1") (pinfunction "VCC(A)_1") (pintype "power_in"))
      (node (ref "U14") (pin "1") (pinfunction "VCC(A)_1") (pintype "power_in"))
      (node (ref "U17") (pin "1") (pinfunction "VCC(A)_1") (pintype "power_in"))
      (node (ref "U4") (pin "1") (pinfunction "VCC(A)_1") (pintype "power_in"))
      (node (ref "U6") (pin "1") (pinfunction "VCC(A)_1") (pintype "power_in"))
    )
    (net (code "43") (name "VSYS") (class "Default")
      (node (ref "C11") (pin "2") (pinfunction "2_2") (pintype "passive"))
      (node (ref "C18") (pin "2") (pinfunction "2_2") (pintype "passive"))
      (node (ref "C30") (pin "2") (pinfunction "2_2") (pintype "passive"))
      (node (ref "C32") (pin "2") (pinfunction "2_2") (pintype "passive"))
      (node (ref "C36") (pin "2") (pinfunction "2_2") (pintype "passive"))
      (node (ref "C43") (pin "2") (pinfunction "2_2") (pintype "passive"))
      (node (ref "R72") (pin "2") (pinfunction "2_2") (pintype "passive"))
      (node (ref "R73") (pin "2") (pinfunction "2_2") (pintype "passive"))
      (node (ref "R74") (pin "2") (pinfunction "2_2") (pintype "passive"))
      (node (ref "R75") (pin "2") (pinfunction "2_2") (pintype "passive"))
      (node (ref "R76") (pin "2") (pinfunction "2_2") (pintype "passive"))
      (node (ref "R77") (pin "2") (pinfunction "2_2") (pintype "passive"))
      (node (ref "R78") (pin "2") (pinfunction "2_2") (pintype "passive"))
      (node (ref "R79") (pin "2") (pinfunction "2_2") (pintype "passive"))
      (node (ref "R80") (pin "2") (pinfunction "2_2") (pintype "passive"))
      (node (ref "U11") (pin "8") (pinfunction "VCC(B)_8") (pintype "power_in"))
      (node (ref "U12") (pin "8") (pinfunction "VCC(B)_8") (pintype "power_in"))
      (node (ref "U14") (pin "8") (pinfunction "VCC(B)_8") (pintype "power_in"))
      (node (ref "U17") (pin "8") (pinfunction "VCC(B)_8") (pintype "power_in"))
      (node (ref "U4") (pin "8") (pinfunction "VCC(B)_8") (pintype "power_in"))
      (node (ref "U6") (pin "8") (pinfunction "VCC(B)_8") (pintype "power_in"))
    )
  )
)
